# micros.net
KiCad netlist of a schematic drawn in Altium Designer
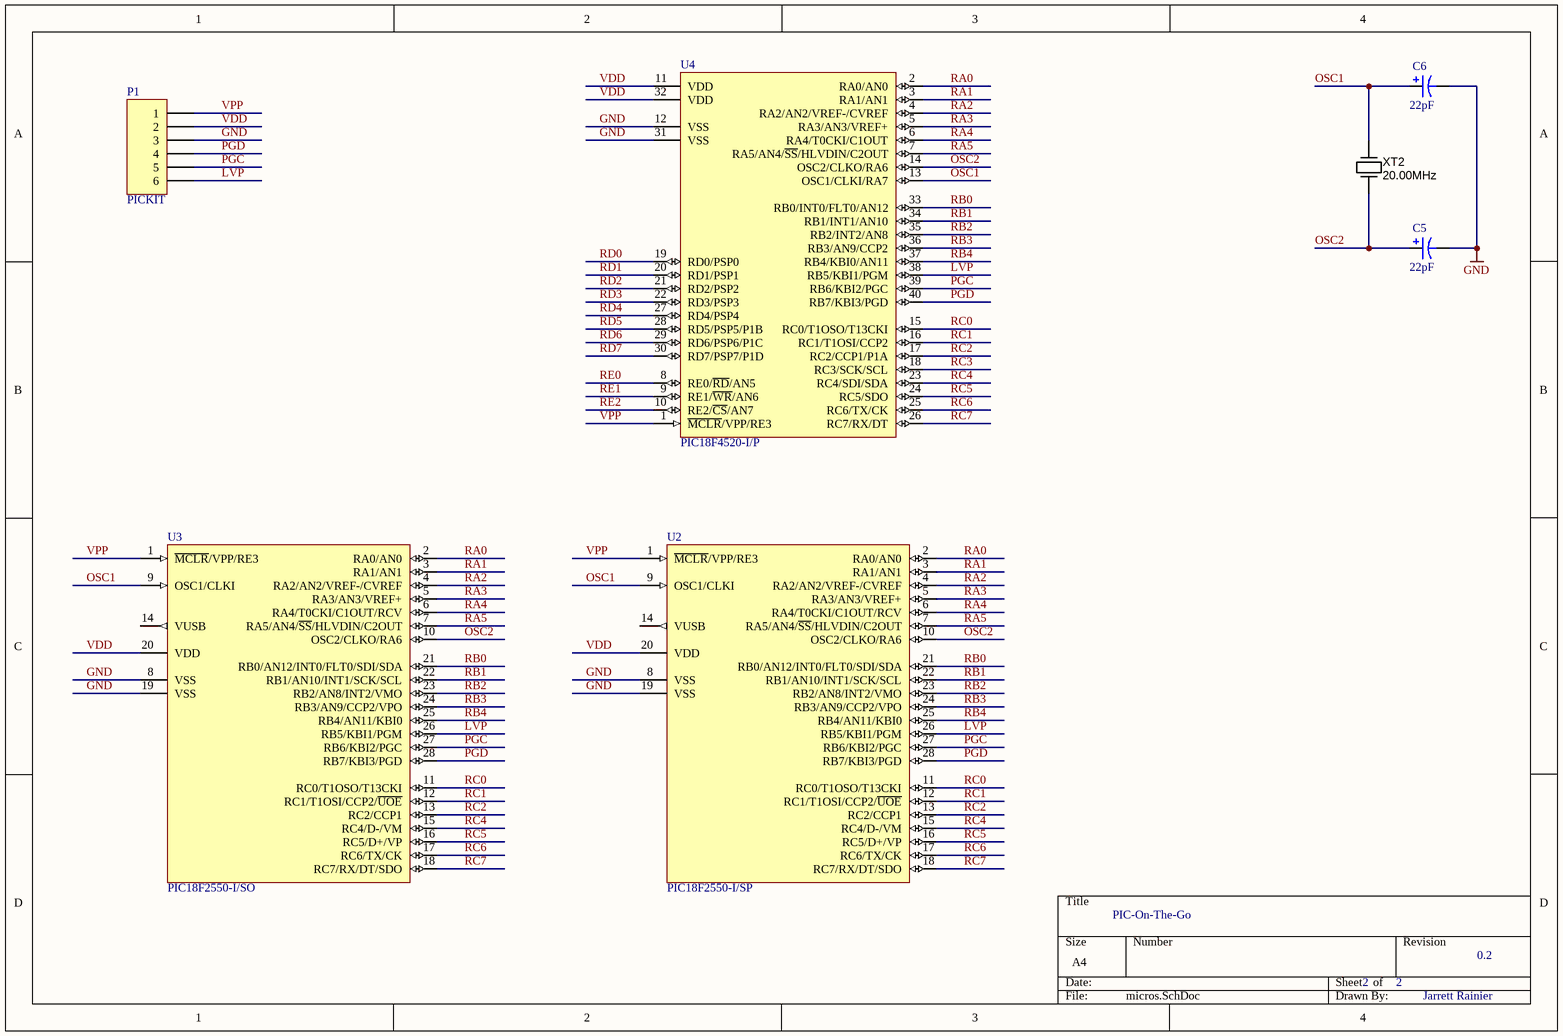
[diagram p0: micros.SchDoc]

(export (version "E")
  (design (tool "Eeschema 10.0.6"))
  (components
    (comp (ref "C5")
      (value "22pF")
      (footprint "C0805")
      (description "Polarized Capacitor (Surface Mount)")
      (fields (field (name "Comment") "Cap Pol3") (field (name "PUBLISHER") "Altium Limited"))
      (libsource (lib "Miscellaneous Devices") (part "Cap Pol3"))
    )
    (comp (ref "C6")
      (value "22pF")
      (footprint "C0805")
      (description "Polarized Capacitor (Surface Mount)")
      (fields (field (name "Comment") "Cap Pol3") (field (name "PUBLISHER") "Altium Limited"))
      (libsource (lib "Miscellaneous Devices") (part "Cap Pol3"))
    )
    (comp (ref "P1")
      (value "PICKIT")
      (footprint "HDR1X6")
      (description "Header, 6-Pin")
      (fields (field (name "PUBLISHER") "Altium Limited"))
      (libsource (lib "Miscellaneous Connectors") (part "Header 6"))
    )
    (comp (ref "U2")
      (value "PIC18F2550-I/SP")
      (footprint "SPDIP300-SP28")
      (fields (field (name "PUBLISHER") "Altium Limited"))
      (libsource (lib "Microchip Microcontroller 8-Bit PIC18") (part "PIC18F2550-I/SP"))
    )
    (comp (ref "U3")
      (value "PIC18F2550-I/SO")
      (footprint "SOIC-SO28_N")
      (fields (field (name "PUBLISHER") "Altium Limited"))
      (libsource (lib "Microchip Microcontroller 8-Bit PIC18") (part "PIC18F2550-I/SO"))
    )
    (comp (ref "U4")
      (value "PIC18F4520-I/P")
      (footprint "PDIP600-P40")
      (fields (field (name "PUBLISHER") "Altium Limited"))
      (libsource (lib "Microchip Microcontroller 8-Bit PIC18") (part "PIC18F4520-I/P"))
    )
    (comp (ref "XT2")
      (value "20.00MHz")
      (footprint "CRYSTAL_HC49-US-SM")
      (description "Resonator Ceramic 20.00 MHz 30ppm")
      (libsource (lib "PBL - Resonators") (part "Crystal_6MHz_HC49/US"))
    )
  )
  (nets
    (net (code "1") (name "/LVP") (class "Default")
      (node (ref "P1") (pin "6") (pinfunction "6_6") (pintype "passive"))
      (node (ref "U2") (pin "26") (pinfunction "RB5/KBI1/PGM_26") (pintype "bidirectional"))
      (node (ref "U3") (pin "26") (pinfunction "RB5/KBI1/PGM_26") (pintype "bidirectional"))
      (node (ref "U4") (pin "38") (pinfunction "RB5/KBI1/PGM_38") (pintype "bidirectional"))
    )
    (net (code "2") (name "/OSC1") (class "Default")
      (node (ref "C6") (pin "1") (pinfunction "1_1") (pintype "passive"))
      (node (ref "U2") (pin "9") (pinfunction "OSC1/CLKI_9") (pintype "input"))
      (node (ref "U3") (pin "9") (pinfunction "OSC1/CLKI_9") (pintype "input"))
      (node (ref "U4") (pin "13") (pinfunction "OSC1/CLKI/RA7_13") (pintype "bidirectional"))
      (node (ref "XT2") (pin "2") (pinfunction "OUT_2") (pintype "passive"))
    )
    (net (code "3") (name "/OSC2") (class "Default")
      (node (ref "C5") (pin "1") (pinfunction "1_1") (pintype "passive"))
      (node (ref "U2") (pin "10") (pinfunction "OSC2/CLKO/RA6_10") (pintype "bidirectional"))
      (node (ref "U3") (pin "10") (pinfunction "OSC2/CLKO/RA6_10") (pintype "bidirectional"))
      (node (ref "U4") (pin "14") (pinfunction "OSC2/CLKO/RA6_14") (pintype "bidirectional"))
      (node (ref "XT2") (pin "1") (pinfunction "IN_1") (pintype "passive"))
    )
    (net (code "4") (name "/PGC") (class "Default")
      (node (ref "P1") (pin "5") (pinfunction "5_5") (pintype "passive"))
      (node (ref "U2") (pin "27") (pinfunction "RB6/KBI2/PGC_27") (pintype "bidirectional"))
      (node (ref "U3") (pin "27") (pinfunction "RB6/KBI2/PGC_27") (pintype "bidirectional"))
      (node (ref "U4") (pin "39") (pinfunction "RB6/KBI2/PGC_39") (pintype "bidirectional"))
    )
    (net (code "5") (name "/PGD") (class "Default")
      (node (ref "P1") (pin "4") (pinfunction "4_4") (pintype "passive"))
      (node (ref "U2") (pin "28") (pinfunction "RB7/KBI3/PGD_28") (pintype "bidirectional"))
      (node (ref "U3") (pin "28") (pinfunction "RB7/KBI3/PGD_28") (pintype "bidirectional"))
      (node (ref "U4") (pin "40") (pinfunction "RB7/KBI3/PGD_40") (pintype "bidirectional"))
    )
    (net (code "6") (name "/RA0") (class "Default")
      (node (ref "U2") (pin "2") (pinfunction "RA0/AN0_2") (pintype "bidirectional"))
      (node (ref "U3") (pin "2") (pinfunction "RA0/AN0_2") (pintype "bidirectional"))
      (node (ref "U4") (pin "2") (pinfunction "RA0/AN0_2") (pintype "bidirectional"))
    )
    (net (code "7") (name "/RA1") (class "Default")
      (node (ref "U2") (pin "3") (pinfunction "RA1/AN1_3") (pintype "bidirectional"))
      (node (ref "U3") (pin "3") (pinfunction "RA1/AN1_3") (pintype "bidirectional"))
      (node (ref "U4") (pin "3") (pinfunction "RA1/AN1_3") (pintype "bidirectional"))
    )
    (net (code "8") (name "/RA2") (class "Default")
      (node (ref "U2") (pin "4") (pinfunction "RA2/AN2/VREF-/CVREF_4") (pintype "bidirectional"))
      (node (ref "U3") (pin "4") (pinfunction "RA2/AN2/VREF-/CVREF_4") (pintype "bidirectional"))
      (node (ref "U4") (pin "4") (pinfunction "RA2/AN2/VREF-/CVREF_4") (pintype "bidirectional"))
    )
    (net (code "9") (name "/RA3") (class "Default")
      (node (ref "U2") (pin "5") (pinfunction "RA3/AN3/VREF+_5") (pintype "bidirectional"))
      (node (ref "U3") (pin "5") (pinfunction "RA3/AN3/VREF+_5") (pintype "bidirectional"))
      (node (ref "U4") (pin "5") (pinfunction "RA3/AN3/VREF+_5") (pintype "bidirectional"))
    )
    (net (code "10") (name "/RA4") (class "Default")
      (node (ref "U2") (pin "6") (pinfunction "RA4/T0CKI/C1OUT/RCV_6") (pintype "bidirectional"))
      (node (ref "U3") (pin "6") (pinfunction "RA4/T0CKI/C1OUT/RCV_6") (pintype "bidirectional"))
      (node (ref "U4") (pin "6") (pinfunction "RA4/T0CKI/C1OUT_6") (pintype "bidirectional"))
    )
    (net (code "11") (name "/RA5") (class "Default")
      (node (ref "U2") (pin "7") (pinfunction "RA5/AN4/~{SS}/HLVDIN/C2OUT_7") (pintype "bidirectional"))
      (node (ref "U3") (pin "7") (pinfunction "RA5/AN4/~{SS}/HLVDIN/C2OUT_7") (pintype "bidirectional"))
      (node (ref "U4") (pin "7") (pinfunction "RA5/AN4/~{SS}/HLVDIN/C2OUT_7") (pintype "bidirectional"))
    )
    (net (code "12") (name "/RB0") (class "Default")
      (node (ref "U2") (pin "21") (pinfunction "RB0/AN12/INT0/FLT0/SDI/SDA_21") (pintype "bidirectional"))
      (node (ref "U3") (pin "21") (pinfunction "RB0/AN12/INT0/FLT0/SDI/SDA_21") (pintype "bidirectional"))
      (node (ref "U4") (pin "33") (pinfunction "RB0/INT0/FLT0/AN12_33") (pintype "bidirectional"))
    )
    (net (code "13") (name "/RB1") (class "Default")
      (node (ref "U2") (pin "22") (pinfunction "RB1/AN10/INT1/SCK/SCL_22") (pintype "bidirectional"))
      (node (ref "U3") (pin "22") (pinfunction "RB1/AN10/INT1/SCK/SCL_22") (pintype "bidirectional"))
      (node (ref "U4") (pin "34") (pinfunction "RB1/INT1/AN10_34") (pintype "bidirectional"))
    )
    (net (code "14") (name "/RB2") (class "Default")
      (node (ref "U2") (pin "23") (pinfunction "RB2/AN8/INT2/VMO_23") (pintype "bidirectional"))
      (node (ref "U3") (pin "23") (pinfunction "RB2/AN8/INT2/VMO_23") (pintype "bidirectional"))
      (node (ref "U4") (pin "35") (pinfunction "RB2/INT2/AN8_35") (pintype "bidirectional"))
    )
    (net (code "15") (name "/RB3") (class "Default")
      (node (ref "U2") (pin "24") (pinfunction "RB3/AN9/CCP2/VPO_24") (pintype "bidirectional"))
      (node (ref "U3") (pin "24") (pinfunction "RB3/AN9/CCP2/VPO_24") (pintype "bidirectional"))
      (node (ref "U4") (pin "36") (pinfunction "RB3/AN9/CCP2_36") (pintype "bidirectional"))
    )
    (net (code "16") (name "/RB4") (class "Default")
      (node (ref "U2") (pin "25") (pinfunction "RB4/AN11/KBI0_25") (pintype "bidirectional"))
      (node (ref "U3") (pin "25") (pinfunction "RB4/AN11/KBI0_25") (pintype "bidirectional"))
      (node (ref "U4") (pin "37") (pinfunction "RB4/KBI0/AN11_37") (pintype "bidirectional"))
    )
    (net (code "17") (name "/RC0") (class "Default")
      (node (ref "U2") (pin "11") (pinfunction "RC0/T1OSO/T13CKI_11") (pintype "bidirectional"))
      (node (ref "U3") (pin "11") (pinfunction "RC0/T1OSO/T13CKI_11") (pintype "bidirectional"))
      (node (ref "U4") (pin "15") (pinfunction "RC0/T1OSO/T13CKI_15") (pintype "bidirectional"))
    )
    (net (code "18") (name "/RC1") (class "Default")
      (node (ref "U2") (pin "12") (pinfunction "RC1/T1OSI/CCP2/~{UOE}_12") (pintype "bidirectional"))
      (node (ref "U3") (pin "12") (pinfunction "RC1/T1OSI/CCP2/~{UOE}_12") (pintype "bidirectional"))
      (node (ref "U4") (pin "16") (pinfunction "RC1/T1OSI/CCP2_16") (pintype "bidirectional"))
    )
    (net (code "19") (name "/RC2") (class "Default")
      (node (ref "U2") (pin "13") (pinfunction "RC2/CCP1_13") (pintype "bidirectional"))
      (node (ref "U3") (pin "13") (pinfunction "RC2/CCP1_13") (pintype "bidirectional"))
      (node (ref "U4") (pin "17") (pinfunction "RC2/CCP1/P1A_17") (pintype "bidirectional"))
    )
    (net (code "20") (name "/RC3") (class "Default")
      (node (ref "U4") (pin "18") (pinfunction "RC3/SCK/SCL_18") (pintype "bidirectional"))
    )
    (net (code "21") (name "/RC4") (class "Default")
      (node (ref "U2") (pin "15") (pinfunction "RC4/D-/VM_15") (pintype "bidirectional"))
      (node (ref "U3") (pin "15") (pinfunction "RC4/D-/VM_15") (pintype "bidirectional"))
      (node (ref "U4") (pin "23") (pinfunction "RC4/SDI/SDA_23") (pintype "bidirectional"))
    )
    (net (code "22") (name "/RC5") (class "Default")
      (node (ref "U2") (pin "16") (pinfunction "RC5/D+/VP_16") (pintype "bidirectional"))
      (node (ref "U3") (pin "16") (pinfunction "RC5/D+/VP_16") (pintype "bidirectional"))
      (node (ref "U4") (pin "24") (pinfunction "RC5/SDO_24") (pintype "bidirectional"))
    )
    (net (code "23") (name "/RC6") (class "Default")
      (node (ref "U2") (pin "17") (pinfunction "RC6/TX/CK_17") (pintype "bidirectional"))
      (node (ref "U3") (pin "17") (pinfunction "RC6/TX/CK_17") (pintype "bidirectional"))
      (node (ref "U4") (pin "25") (pinfunction "RC6/TX/CK_25") (pintype "bidirectional"))
    )
    (net (code "24") (name "/RC7") (class "Default")
      (node (ref "U2") (pin "18") (pinfunction "RC7/RX/DT/SDO_18") (pintype "bidirectional"))
      (node (ref "U3") (pin "18") (pinfunction "RC7/RX/DT/SDO_18") (pintype "bidirectional"))
      (node (ref "U4") (pin "26") (pinfunction "RC7/RX/DT_26") (pintype "bidirectional"))
    )
    (net (code "25") (name "/RD0") (class "Default")
      (node (ref "U4") (pin "19") (pinfunction "RD0/PSP0_19") (pintype "bidirectional"))
    )
    (net (code "26") (name "/RD1") (class "Default")
      (node (ref "U4") (pin "20") (pinfunction "RD1/PSP1_20") (pintype "bidirectional"))
    )
    (net (code "27") (name "/RD2") (class "Default")
      (node (ref "U4") (pin "21") (pinfunction "RD2/PSP2_21") (pintype "bidirectional"))
    )
    (net (code "28") (name "/RD3") (class "Default")
      (node (ref "U4") (pin "22") (pinfunction "RD3/PSP3_22") (pintype "bidirectional"))
    )
    (net (code "29") (name "/RD4") (class "Default")
      (node (ref "U4") (pin "27") (pinfunction "RD4/PSP4_27") (pintype "bidirectional"))
    )
    (net (code "30") (name "/RD5") (class "Default")
      (node (ref "U4") (pin "28") (pinfunction "RD5/PSP5/P1B_28") (pintype "bidirectional"))
    )
    (net (code "31") (name "/RD6") (class "Default")
      (node (ref "U4") (pin "29") (pinfunction "RD6/PSP6/P1C_29") (pintype "bidirectional"))
    )
    (net (code "32") (name "/RD7") (class "Default")
      (node (ref "U4") (pin "30") (pinfunction "RD7/PSP7/P1D_30") (pintype "bidirectional"))
    )
    (net (code "33") (name "/RE0") (class "Default")
      (node (ref "U4") (pin "8") (pinfunction "RE0/~{RD}/AN5_8") (pintype "bidirectional"))
    )
    (net (code "34") (name "/RE1") (class "Default")
      (node (ref "U4") (pin "9") (pinfunction "RE1/~{WR}/AN6_9") (pintype "bidirectional"))
    )
    (net (code "35") (name "/RE2") (class "Default")
      (node (ref "U4") (pin "10") (pinfunction "RE2/~{CS}/AN7_10") (pintype "bidirectional"))
    )
    (net (code "36") (name "/VDD") (class "Default")
      (node (ref "P1") (pin "2") (pinfunction "2_2") (pintype "passive"))
      (node (ref "U2") (pin "20") (pinfunction "VDD_20") (pintype "power_in"))
      (node (ref "U3") (pin "20") (pinfunction "VDD_20") (pintype "power_in"))
      (node (ref "U4") (pin "11") (pinfunction "VDD_11") (pintype "power_in"))
      (node (ref "U4") (pin "32") (pinfunction "VDD_32") (pintype "power_in"))
    )
    (net (code "37") (name "/VPP") (class "Default")
      (node (ref "P1") (pin "1") (pinfunction "1_1") (pintype "passive"))
      (node (ref "U2") (pin "1") (pinfunction "~{MCLR}/VPP/RE3_1") (pintype "input"))
      (node (ref "U3") (pin "1") (pinfunction "~{MCLR}/VPP/RE3_1") (pintype "input"))
      (node (ref "U4") (pin "1") (pinfunction "~{MCLR}/VPP/RE3_1") (pintype "input"))
    )
    (net (code "38") (name "GND") (class "Default")
      (node (ref "C5") (pin "2") (pinfunction "2_2") (pintype "passive"))
      (node (ref "C6") (pin "2") (pinfunction "2_2") (pintype "passive"))
      (node (ref "P1") (pin "3") (pinfunction "3_3") (pintype "passive"))
      (node (ref "U2") (pin "19") (pinfunction "VSS_19") (pintype "power_in"))
      (node (ref "U2") (pin "8") (pinfunction "VSS_8") (pintype "power_in"))
      (node (ref "U3") (pin "19") (pinfunction "VSS_19") (pintype "power_in"))
      (node (ref "U3") (pin "8") (pinfunction "VSS_8") (pintype "power_in"))
      (node (ref "U4") (pin "12") (pinfunction "VSS_12") (pintype "power_in"))
      (node (ref "U4") (pin "31") (pinfunction "VSS_31") (pintype "power_in"))
    )
    (net (code "39") (name "unconnected-(U2-VUSB-Pad14)") (class "Default")
      (node (ref "U2") (pin "14") (pinfunction "VUSB_14") (pintype "output"))
    )
    (net (code "40") (name "unconnected-(U3-VUSB-Pad14)") (class "Default")
      (node (ref "U3") (pin "14") (pinfunction "VUSB_14") (pintype "output"))
    )
  )
)
